# quadcopter.net
KiCad netlist of a schematic drawn in EAGLE
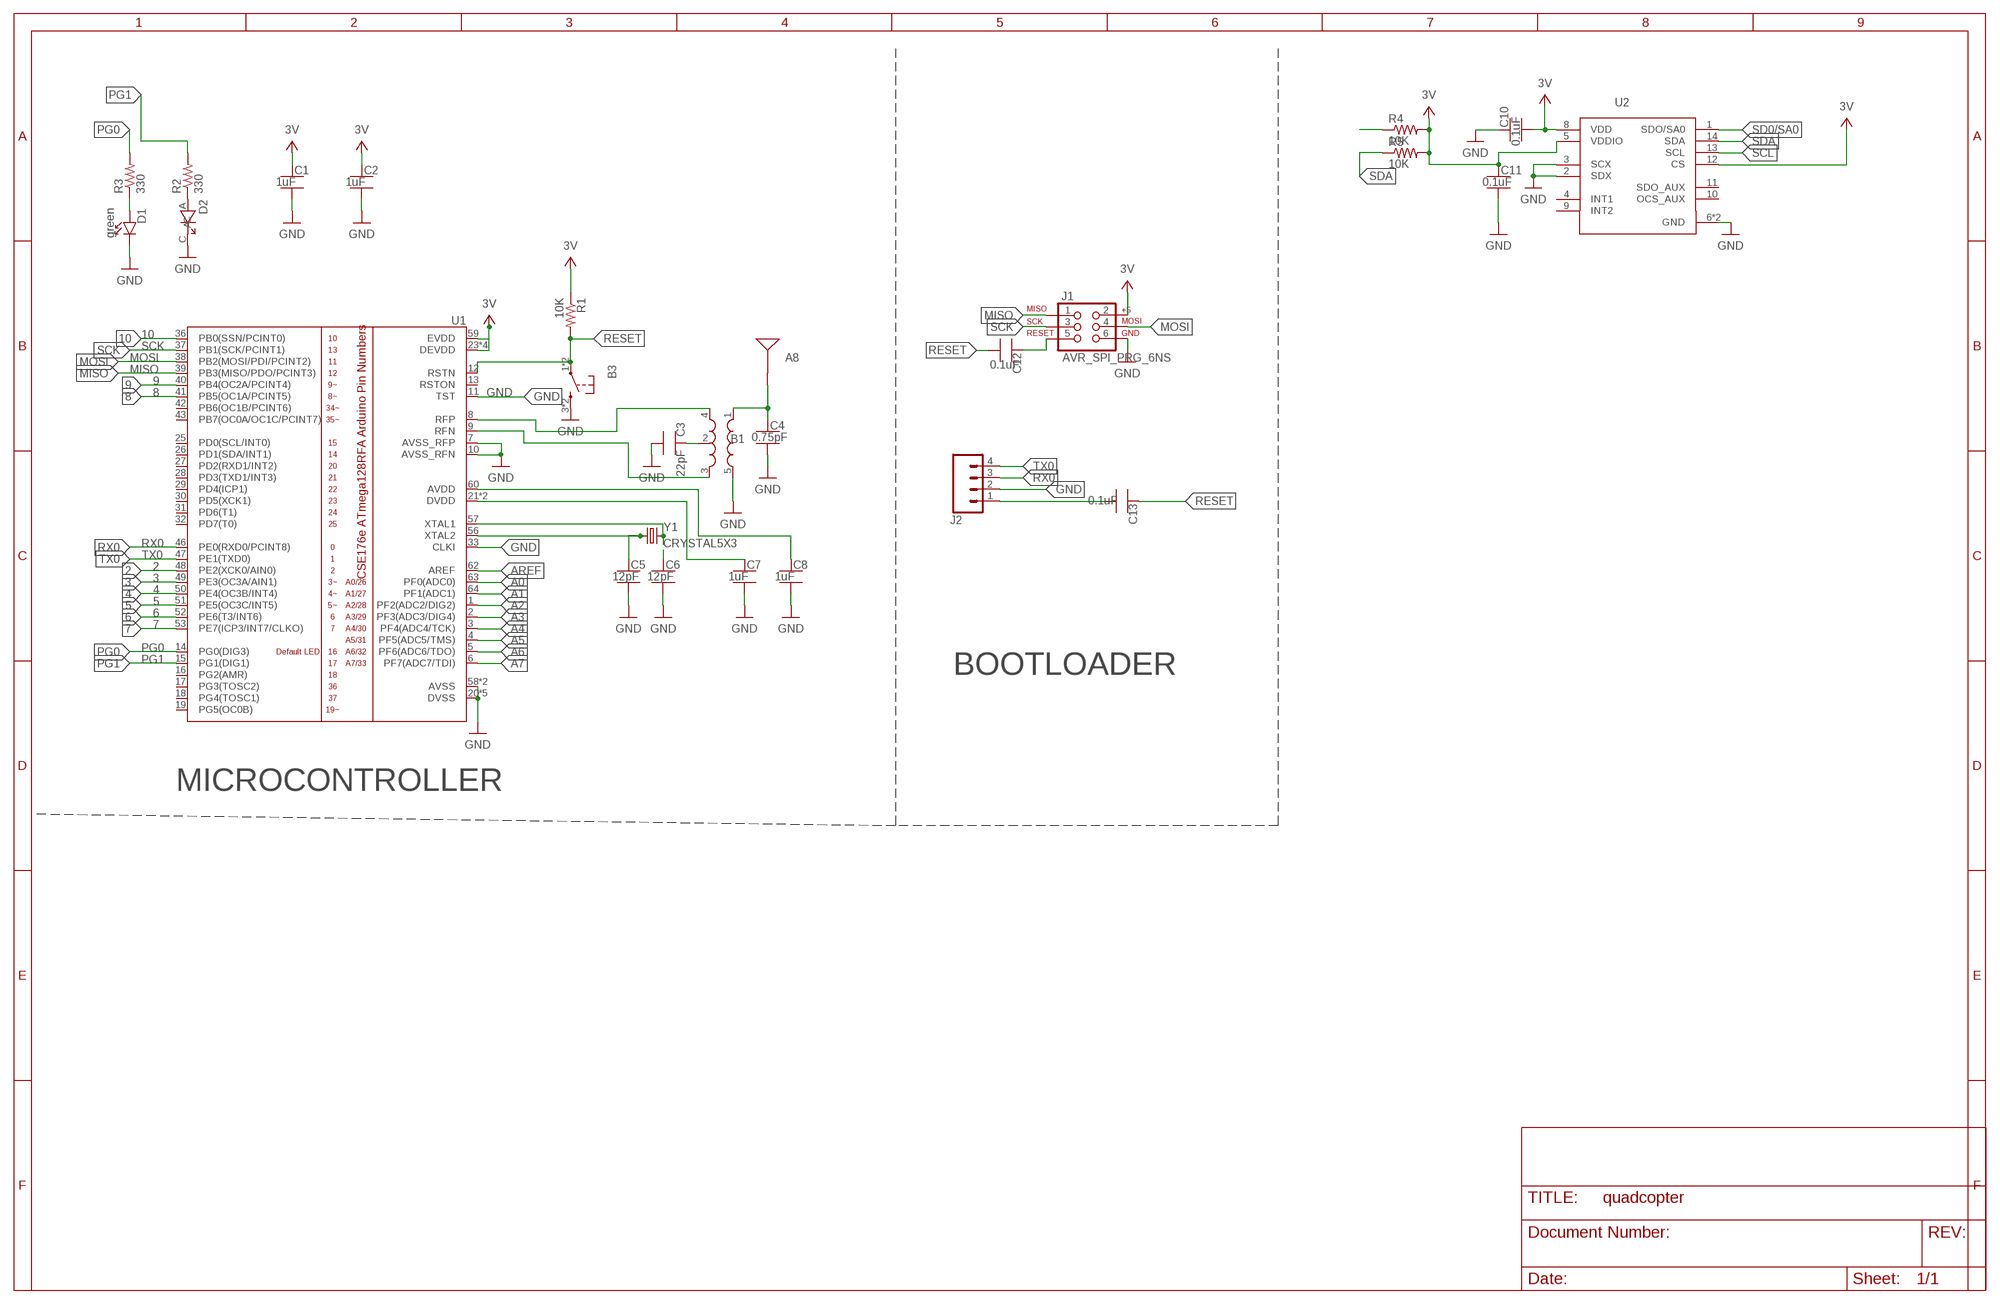
[diagram p0: schematic, sheet 1]

(export (version "E")
  (design (tool "Eeschema 10.0.6"))
  (components
    (comp (ref "A8")
      (value "ANTENNA-BOARD")
      (footprint "eagle-import:ANT_PCB_2.4GHZ_NRF8001_1.6MM_1OZ")
      (fields (field (name "MFR") "NA") (field (name "CREATOR") "Swanson"))
      (libsource (lib "eagle-import") (part "ANTENNA-BOARD"))
    )
    (comp (ref "B1")
      (value "BALUN0805")
      (footprint "eagle-import:BALUN")
      (fields
        (field (name "MFR") "Wurth Electronics Inc.")
        (field (name "MPN") "748421245")
        (field (name "CREATOR") "Swanson")
        (field (name "REVIEWER") "Swanson")
      )
      (libsource (lib "eagle-import") (part "BALUN0805"))
    )
    (comp (ref "B3")
      (value "PUSHBUTTON_SMD-VERTICAL-1")
      (footprint "eagle-import:TE_FSM8JSMA_HS")
      (fields
        (field (name "MFR") "TE Connectivity Alcoswitch Switches")
        (field (name "MPN") "FSM4JSMA")
        (field (name "CREATOR") "Swanson")
        (field (name "REVIEWER") "Swanson")
      )
      (libsource (lib "eagle-import") (part "PUSHBUTTON_SMD-VERTICAL-1"))
    )
    (comp (ref "C1")
      (value "1uF")
      (footprint "eagle-import:CAPC2012X140_HS")
      (fields
        (field (name "MFR") "Taiyo Yuden")
        (field (name "MPN") "TMK212B7105KG-T")
        (field (name "CREATOR") "Swanson")
        (field (name "REVIEWER") "Swanson")
      )
      (libsource (lib "eagle-import") (part "CAPACITOR-NP_SMD-2012-0805_CERAMIC-1UF"))
    )
    (comp (ref "C2")
      (value "1uF")
      (footprint "eagle-import:CAPC2012X140_HS")
      (fields
        (field (name "MFR") "Taiyo Yuden")
        (field (name "MPN") "TMK212B7105KG-T")
        (field (name "CREATOR") "Swanson")
        (field (name "REVIEWER") "Swanson")
      )
      (libsource (lib "eagle-import") (part "CAPACITOR-NP_SMD-2012-0805_CERAMIC-1UF"))
    )
    (comp (ref "C3")
      (value "22pF")
      (footprint "eagle-import:CAPC2012X140_HS")
      (fields
        (field (name "MFR") "Murata Electronics")
        (field (name "MPN") "GRM21A5C2E220JW01D")
        (field (name "CREATOR") "Swanson")
        (field (name "REVIEWER") "Swanson")
      )
      (libsource (lib "eagle-import") (part "CAPACITOR-NP_SMD-2012-0805_CERAMIC-22PF"))
    )
    (comp (ref "C4")
      (value "0.75pF")
      (footprint "eagle-import:CAPC2012X140_HS")
      (fields
        (field (name "MFR") "Murata Electronics")
        (field (name "MPN") "GQM2195C2AR75CB01D")
        (field (name "CREATOR") "Swanson")
        (field (name "REVIEWER") "Swanson")
      )
      (libsource (lib "eagle-import") (part "CAPACITOR-NP_SMD-2012-0805_CERAMIC-0.75PF"))
    )
    (comp (ref "C5")
      (value "12pF")
      (footprint "eagle-import:CAPC2012X140_HS")
      (fields
        (field (name "MFR") "Murata Electronics")
        (field (name "MPN") "GRM21A5C2E120JW01D")
        (field (name "CREATOR") "Swanson")
        (field (name "REVIEWER") "Swanson")
      )
      (libsource (lib "eagle-import") (part "CAPACITOR-NP_SMD-2012-0805_CERAMIC-12PF"))
    )
    (comp (ref "C6")
      (value "12pF")
      (footprint "eagle-import:CAPC2012X140_HS")
      (fields
        (field (name "MFR") "Murata Electronics")
        (field (name "MPN") "GRM21A5C2E120JW01D")
        (field (name "CREATOR") "Swanson")
        (field (name "REVIEWER") "Swanson")
      )
      (libsource (lib "eagle-import") (part "CAPACITOR-NP_SMD-2012-0805_CERAMIC-12PF"))
    )
    (comp (ref "C7")
      (value "1uF")
      (footprint "eagle-import:CAPC2012X140_HS")
      (fields
        (field (name "MFR") "Taiyo Yuden")
        (field (name "MPN") "TMK212B7105KG-T")
        (field (name "CREATOR") "Swanson")
        (field (name "REVIEWER") "Swanson")
      )
      (libsource (lib "eagle-import") (part "CAPACITOR-NP_SMD-2012-0805_CERAMIC-1UF"))
    )
    (comp (ref "C8")
      (value "1uF")
      (footprint "eagle-import:CAPC2012X140_HS")
      (fields
        (field (name "MFR") "Taiyo Yuden")
        (field (name "MPN") "TMK212B7105KG-T")
        (field (name "CREATOR") "Swanson")
        (field (name "REVIEWER") "Swanson")
      )
      (libsource (lib "eagle-import") (part "CAPACITOR-NP_SMD-2012-0805_CERAMIC-1UF"))
    )
    (comp (ref "C10")
      (value "0.1uF")
      (footprint "eagle-import:CAPC2012X140_HS")
      (fields
        (field (name "MFR") "TDK Corporation")
        (field (name "MPN") "C2012X7R2A104K125AA")
        (field (name "CREATOR") "Swanson")
        (field (name "REVIEWER") "Swanson")
      )
      (libsource (lib "eagle-import") (part "CAPACITOR-NP_SMD-2012-0805_CERAMIC-0.1UF"))
    )
    (comp (ref "C11")
      (value "0.1uF")
      (footprint "eagle-import:CAPC2012X140_HS")
      (fields
        (field (name "MFR") "TDK Corporation")
        (field (name "MPN") "C2012X7R2A104K125AA")
        (field (name "CREATOR") "Swanson")
        (field (name "REVIEWER") "Swanson")
      )
      (libsource (lib "eagle-import") (part "CAPACITOR-NP_SMD-2012-0805_CERAMIC-0.1UF"))
    )
    (comp (ref "C12")
      (value "0.1uF")
      (footprint "eagle-import:CAPC2012X140_HS")
      (fields
        (field (name "MFR") "TDK Corporation")
        (field (name "MPN") "C2012X7R2A104K125AA")
        (field (name "CREATOR") "Swanson")
        (field (name "REVIEWER") "Swanson")
      )
      (libsource (lib "eagle-import") (part "CAPACITOR-NP_SMD-2012-0805_CERAMIC-0.1UF"))
    )
    (comp (ref "C13")
      (value "0.1uF")
      (footprint "eagle-import:CAPC2012X140_HS")
      (fields
        (field (name "MFR") "TDK Corporation")
        (field (name "MPN") "C2012X7R2A104K125AA")
        (field (name "CREATOR") "Swanson")
        (field (name "REVIEWER") "Swanson")
      )
      (libsource (lib "eagle-import") (part "CAPACITOR-NP_SMD-2012-0805_CERAMIC-0.1UF"))
    )
    (comp (ref "D1")
      (value "green")
      (footprint "eagle-import:LEDSC125X200X120-2_HS")
      (fields
        (field (name "MFR") "Lite-On Inc")
        (field (name "MPN") "LTST-C170GKT")
        (field (name "CREATOR") "Swanson")
        (field (name "REVIEWER") "Swanson")
      )
      (libsource (lib "eagle-import") (part "DIODE-LED_SMD-2012-0805-GREEN"))
    )
    (comp (ref "D2")
      (value "LED-RED-160-1178-1-ND")
      (footprint "eagle-import:LED_160-1178-1-ND")
      (fields (field (name "CREATOR") "KaustubhKanagalekar"))
      (libsource (lib "eagle-import") (part "LED-RED-160-1178-1-ND"))
    )
    (comp (ref "J1")
      (value "AVR_SPI_PRG_6NS")
      (footprint "eagle-import:2X3-NS")
      (fields
        (field (name "MFR") "Amphenol FCI")
        (field (name "MPN") "67997-206HLF")
        (field (name "CREATOR") "Swanson")
        (field (name "REVIEWER") "Swanson")
      )
      (libsource (lib "eagle-import") (part "AVR_SPI_PRG_6NS"))
    )
    (comp (ref "J2")
      (value "HEADER-4POS-2X2-0.1IN-FEMALE-SMD-BOTTOM-ENTRY")
      (footprint "eagle-import:CONN4_969973-2")
      (fields (field (name "MANUFACTURER_PART_NUMBER") "9699732") (field (name "CREATOR") "DIGIKEY"))
      (libsource (lib "eagle-import") (part "HEADER-4POS-2X2-0.1IN-FEMALE-SMD-BOTTOM-ENTRY"))
    )
    (comp (ref "R1")
      (value "10K")
      (footprint "eagle-import:RESC2012X60_HS")
      (fields
        (field (name "MFR") "Yageo")
        (field (name "MPN") "RC0805JR-0710KL")
        (field (name "CREATOR") "Swanson")
        (field (name "REVIEWER") "Swanson")
      )
      (libsource (lib "eagle-import") (part "RESISTOR_SMD-2012-0805-10K"))
    )
    (comp (ref "R2")
      (value "330")
      (footprint "eagle-import:RESC2012X60_HS")
      (fields
        (field (name "MFR") "Yageo")
        (field (name "MPN") "RC0805JR-07330RL")
        (field (name "CREATOR") "Swanson")
        (field (name "REVIEWER") "Swanson")
      )
      (libsource (lib "eagle-import") (part "RESISTOR_SMD-2012-0805-330"))
    )
    (comp (ref "R3")
      (value "330")
      (footprint "eagle-import:RESC2012X60_HS")
      (fields
        (field (name "MFR") "Yageo")
        (field (name "MPN") "RC0805JR-07330RL")
        (field (name "CREATOR") "Swanson")
        (field (name "REVIEWER") "Swanson")
      )
      (libsource (lib "eagle-import") (part "RESISTOR_SMD-2012-0805-330"))
    )
    (comp (ref "R4")
      (value "10K")
      (footprint "eagle-import:RESC2012X60_HS")
      (fields
        (field (name "MFR") "Yageo")
        (field (name "MPN") "RC0805JR-0710KL")
        (field (name "CREATOR") "Swanson")
        (field (name "REVIEWER") "Swanson")
      )
      (libsource (lib "eagle-import") (part "RESISTOR_SMD-2012-0805-10K"))
    )
    (comp (ref "R5")
      (value "10K")
      (footprint "eagle-import:RESC2012X60_HS")
      (fields
        (field (name "MFR") "Yageo")
        (field (name "MPN") "RC0805JR-0710KL")
        (field (name "CREATOR") "Swanson")
        (field (name "REVIEWER") "Swanson")
      )
      (libsource (lib "eagle-import") (part "RESISTOR_SMD-2012-0805-10K"))
    )
    (comp (ref "U1")
      (value "ATMEGA128RFA1")
      (footprint "eagle-import:QFN-64")
      (fields
        (field (name "MFR") "Microchip Technology")
        (field (name "MPN") "ATMEGA128RFA1-ZU")
        (field (name "CREATOR") "Swanson")
        (field (name "REVIEWER") "Swanson")
      )
      (libsource (lib "eagle-import") (part "ATMEGA128RFA1"))
    )
    (comp (ref "U2")
      (value "IMU-LSM6DSOXTR-497-18367-1-ND497-18367-1-ND")
      (footprint "eagle-import:LSM6DS0")
      (fields (field (name "CREATOR") "KaustubhKanagalekar"))
      (libsource (lib "eagle-import") (part "IMU-LSM6DSOXTR-497-18367-1-ND497-18367-1-ND"))
    )
    (comp (ref "Y1")
      (value "CRYSTAL5X3")
      (footprint "eagle-import:CRYSTAL-SMD-5X3")
      (fields
        (field (name "MFR") "Abracon LLC")
        (field (name "MPN") "ABM3B-16.000MHZ-B2-T")
        (field (name "CREATOR") "Swanson")
        (field (name "REVIEWER") "Swanson")
      )
      (libsource (lib "eagle-import") (part "CRYSTAL5X3"))
    )
  )
  (nets
    (net (code "1") (name "2") (class "Default")
      (node (ref "U1") (pin "48") (pinfunction "PE2(XCK0/AIN0)_48") (pintype "bidirectional"))
    )
    (net (code "2") (name "3") (class "Default")
      (node (ref "U1") (pin "49") (pinfunction "PE3(OC3A/AIN1)_49") (pintype "bidirectional"))
    )
    (net (code "3") (name "3V") (class "Default")
      (node (ref "C1") (pin "1") (pinfunction "1_1") (pintype "passive"))
      (node (ref "C10") (pin "2") (pinfunction "2_2") (pintype "passive"))
      (node (ref "C11") (pin "1") (pinfunction "1_1") (pintype "passive"))
      (node (ref "C2") (pin "1") (pinfunction "1_1") (pintype "passive"))
      (node (ref "J1") (pin "2") (pinfunction "2_2") (pintype "passive"))
      (node (ref "R1") (pin "1") (pinfunction "1_1") (pintype "passive"))
      (node (ref "R4") (pin "2") (pinfunction "2_2") (pintype "passive"))
      (node (ref "R5") (pin "2") (pinfunction "2_2") (pintype "passive"))
      (node (ref "U1") (pin "23") (pinfunction "DEVDD_23") (pintype "bidirectional"))
      (node (ref "U1") (pin "34") (pinfunction "DEVDD_34") (pintype "bidirectional"))
      (node (ref "U1") (pin "44") (pinfunction "DEVDD_44") (pintype "bidirectional"))
      (node (ref "U1") (pin "54") (pinfunction "DEVDD_54") (pintype "bidirectional"))
      (node (ref "U1") (pin "59") (pinfunction "EVDD_59") (pintype "bidirectional"))
      (node (ref "U2") (pin "12") (pinfunction "CS_12") (pintype "bidirectional"))
      (node (ref "U2") (pin "5") (pinfunction "VDDIO_5") (pintype "bidirectional"))
      (node (ref "U2") (pin "8") (pinfunction "VDD_8") (pintype "bidirectional"))
    )
    (net (code "4") (name "4") (class "Default")
      (node (ref "U1") (pin "50") (pinfunction "PE4(OC3B/INT4)_50") (pintype "bidirectional"))
    )
    (net (code "5") (name "5") (class "Default")
      (node (ref "U1") (pin "51") (pinfunction "PE5(OC3C/INT5)_51") (pintype "bidirectional"))
    )
    (net (code "6") (name "6") (class "Default")
      (node (ref "U1") (pin "52") (pinfunction "PE6(T3/INT6)_52") (pintype "bidirectional"))
    )
    (net (code "7") (name "7") (class "Default")
      (node (ref "U1") (pin "53") (pinfunction "PE7(ICP3/INT7/CLKO)_53") (pintype "bidirectional"))
    )
    (net (code "8") (name "8") (class "Default")
      (node (ref "U1") (pin "41") (pinfunction "PB5(OC1A/PCINT5)_41") (pintype "bidirectional"))
    )
    (net (code "9") (name "9") (class "Default")
      (node (ref "U1") (pin "40") (pinfunction "PB4(OC2A/PCINT4)_40") (pintype "bidirectional"))
    )
    (net (code "10") (name "10") (class "Default")
      (node (ref "U1") (pin "36") (pinfunction "PB0(SSN/PCINT0)_36") (pintype "bidirectional"))
    )
    (net (code "11") (name "A0") (class "Default")
      (node (ref "U1") (pin "63") (pinfunction "PF0(ADC0)_63") (pintype "bidirectional"))
    )
    (net (code "12") (name "A1") (class "Default")
      (node (ref "U1") (pin "64") (pinfunction "PF1(ADC1)_64") (pintype "bidirectional"))
    )
    (net (code "13") (name "A2") (class "Default")
      (node (ref "U1") (pin "1") (pinfunction "PF2(ADC2/DIG2)_1") (pintype "bidirectional"))
    )
    (net (code "14") (name "A3") (class "Default")
      (node (ref "U1") (pin "2") (pinfunction "PF3(ADC3/DIG4)_2") (pintype "bidirectional"))
    )
    (net (code "15") (name "A4") (class "Default")
      (node (ref "U1") (pin "3") (pinfunction "PF4(ADC4/TCK)_3") (pintype "bidirectional"))
    )
    (net (code "16") (name "A5") (class "Default")
      (node (ref "U1") (pin "4") (pinfunction "PF5(ADC5/TMS)_4") (pintype "bidirectional"))
    )
    (net (code "17") (name "A6") (class "Default")
      (node (ref "U1") (pin "5") (pinfunction "PF6(ADC6/TDO)_5") (pintype "bidirectional"))
    )
    (net (code "18") (name "A7") (class "Default")
      (node (ref "U1") (pin "6") (pinfunction "PF7(ADC7/TDI)_6") (pintype "bidirectional"))
    )
    (net (code "19") (name "AREF") (class "Default")
      (node (ref "U1") (pin "62") (pinfunction "AREF_62") (pintype "bidirectional"))
    )
    (net (code "20") (name "GND") (class "Default")
      (node (ref "B1") (pin "5") (pinfunction "GND_5") (pintype "bidirectional"))
      (node (ref "B3") (pin "3") (pinfunction "2_3") (pintype "passive"))
      (node (ref "B3") (pin "4") (pinfunction "2_4") (pintype "passive"))
      (node (ref "C1") (pin "2") (pinfunction "2_2") (pintype "passive"))
      (node (ref "C10") (pin "1") (pinfunction "1_1") (pintype "passive"))
      (node (ref "C11") (pin "2") (pinfunction "2_2") (pintype "passive"))
      (node (ref "C2") (pin "2") (pinfunction "2_2") (pintype "passive"))
      (node (ref "C3") (pin "2") (pinfunction "2_2") (pintype "passive"))
      (node (ref "C4") (pin "2") (pinfunction "2_2") (pintype "passive"))
      (node (ref "C5") (pin "2") (pinfunction "2_2") (pintype "passive"))
      (node (ref "C6") (pin "2") (pinfunction "2_2") (pintype "passive"))
      (node (ref "C7") (pin "2") (pinfunction "2_2") (pintype "passive"))
      (node (ref "C8") (pin "2") (pinfunction "2_2") (pintype "passive"))
      (node (ref "D1") (pin "C") (pinfunction "C_C") (pintype "passive"))
      (node (ref "D2") (pin "C") (pinfunction "C_C") (pintype "bidirectional"))
      (node (ref "J1") (pin "6") (pinfunction "6_6") (pintype "passive"))
      (node (ref "J2") (pin "2") (pinfunction "2_2") (pintype "bidirectional"))
      (node (ref "U1") (pin "10") (pinfunction "AVSS_RFN_10") (pintype "bidirectional"))
      (node (ref "U1") (pin "11") (pinfunction "TST_11") (pintype "bidirectional"))
      (node (ref "U1") (pin "20") (pinfunction "DVSS_20") (pintype "bidirectional"))
      (node (ref "U1") (pin "24") (pinfunction "DVSS_24") (pintype "bidirectional"))
      (node (ref "U1") (pin "33") (pinfunction "CLKI_33") (pintype "bidirectional"))
      (node (ref "U1") (pin "35") (pinfunction "DVSS_35") (pintype "bidirectional"))
      (node (ref "U1") (pin "45") (pinfunction "DVSS_45") (pintype "bidirectional"))
      (node (ref "U1") (pin "55") (pinfunction "DVSS_55") (pintype "bidirectional"))
      (node (ref "U1") (pin "58") (pinfunction "AVSS_58") (pintype "bidirectional"))
      (node (ref "U1") (pin "61") (pinfunction "AVSS_61") (pintype "bidirectional"))
      (node (ref "U1") (pin "7") (pinfunction "AVSS_RFP_7") (pintype "bidirectional"))
      (node (ref "U2") (pin "2") (pinfunction "SDX_2") (pintype "bidirectional"))
      (node (ref "U2") (pin "3") (pinfunction "SCX_3") (pintype "bidirectional"))
      (node (ref "U2") (pin "6") (pinfunction "GND_6") (pintype "bidirectional"))
      (node (ref "U2") (pin "7") (pinfunction "GND_7") (pintype "bidirectional"))
    )
    (net (code "21") (name "MISO") (class "Default")
      (node (ref "J1") (pin "1") (pinfunction "1_1") (pintype "passive"))
      (node (ref "U1") (pin "39") (pinfunction "PB3(MISO/PDO/PCINT3)_39") (pintype "bidirectional"))
    )
    (net (code "22") (name "MOSI") (class "Default")
      (node (ref "J1") (pin "4") (pinfunction "4_4") (pintype "passive"))
      (node (ref "U1") (pin "38") (pinfunction "PB2(MOSI/PDI/PCINT2)_38") (pintype "bidirectional"))
    )
    (net (code "23") (name "Net-(A8-SIGNAL)") (class "Default")
      (node (ref "A8") (pin "FEED") (pinfunction "SIGNAL_FEED") (pintype "bidirectional"))
      (node (ref "B1") (pin "1") (pinfunction "IN_1") (pintype "bidirectional"))
      (node (ref "C4") (pin "1") (pinfunction "1_1") (pintype "passive"))
    )
    (net (code "24") (name "Net-(B1-GND-Pad2)") (class "Default")
      (node (ref "B1") (pin "2") (pinfunction "GND_2") (pintype "bidirectional"))
      (node (ref "C3") (pin "1") (pinfunction "1_1") (pintype "passive"))
    )
    (net (code "25") (name "Net-(B1-OUT1)") (class "Default")
      (node (ref "B1") (pin "4") (pinfunction "OUT1_4") (pintype "bidirectional"))
      (node (ref "U1") (pin "8") (pinfunction "RFP_8") (pintype "bidirectional"))
    )
    (net (code "26") (name "Net-(B1-OUT2)") (class "Default")
      (node (ref "B1") (pin "3") (pinfunction "OUT2_3") (pintype "bidirectional"))
      (node (ref "U1") (pin "9") (pinfunction "RFN_9") (pintype "bidirectional"))
    )
    (net (code "27") (name "Net-(C7-Pad1)") (class "Default")
      (node (ref "C7") (pin "1") (pinfunction "1_1") (pintype "passive"))
      (node (ref "U1") (pin "21") (pinfunction "DVDD_21") (pintype "bidirectional"))
      (node (ref "U1") (pin "22") (pinfunction "DVDD_22") (pintype "bidirectional"))
    )
    (net (code "28") (name "Net-(C13-Pad2)") (class "Default")
      (node (ref "C13") (pin "2") (pinfunction "2_2") (pintype "passive"))
      (node (ref "J2") (pin "1") (pinfunction "1_1") (pintype "bidirectional"))
    )
    (net (code "29") (name "Net-(D1-PadA)") (class "Default")
      (node (ref "D1") (pin "A") (pinfunction "A_A") (pintype "passive"))
      (node (ref "R3") (pin "1") (pinfunction "1_1") (pintype "passive"))
    )
    (net (code "30") (name "Net-(D2-PadA)") (class "Default")
      (node (ref "D2") (pin "A") (pinfunction "A_A") (pintype "bidirectional"))
      (node (ref "R2") (pin "1") (pinfunction "1_1") (pintype "passive"))
    )
    (net (code "31") (name "Net-(U1-AVDD)") (class "Default")
      (node (ref "C8") (pin "1") (pinfunction "1_1") (pintype "passive"))
      (node (ref "U1") (pin "60") (pinfunction "AVDD_60") (pintype "bidirectional"))
    )
    (net (code "32") (name "Net-(U1-XTAL1)") (class "Default")
      (node (ref "C6") (pin "1") (pinfunction "1_1") (pintype "passive"))
      (node (ref "U1") (pin "57") (pinfunction "XTAL1_57") (pintype "bidirectional"))
      (node (ref "Y1") (pin "3") (pinfunction "2_3") (pintype "passive"))
    )
    (net (code "33") (name "Net-(U1-XTAL2)") (class "Default")
      (node (ref "C5") (pin "1") (pinfunction "1_1") (pintype "passive"))
      (node (ref "U1") (pin "56") (pinfunction "XTAL2_56") (pintype "bidirectional"))
      (node (ref "Y1") (pin "1") (pinfunction "1_1") (pintype "passive"))
    )
    (net (code "34") (name "PG0") (class "Default")
      (node (ref "R3") (pin "2") (pinfunction "2_2") (pintype "passive"))
      (node (ref "U1") (pin "14") (pinfunction "PG0(DIG3)_14") (pintype "bidirectional"))
    )
    (net (code "35") (name "PG1") (class "Default")
      (node (ref "R2") (pin "2") (pinfunction "2_2") (pintype "passive"))
      (node (ref "U1") (pin "15") (pinfunction "PG1(DIG1)_15") (pintype "bidirectional"))
    )
    (net (code "36") (name "RESET") (class "Default")
      (node (ref "B3") (pin "1") (pinfunction "1_1") (pintype "passive"))
      (node (ref "B3") (pin "2") (pinfunction "1_2") (pintype "passive"))
      (node (ref "C12") (pin "1") (pinfunction "1_1") (pintype "passive"))
      (node (ref "C13") (pin "1") (pinfunction "1_1") (pintype "passive"))
      (node (ref "J1") (pin "5") (pinfunction "5_5") (pintype "passive"))
      (node (ref "R1") (pin "2") (pinfunction "2_2") (pintype "passive"))
      (node (ref "U1") (pin "12") (pinfunction "RSTN_12") (pintype "bidirectional"))
    )
    (net (code "37") (name "RX0") (class "Default")
      (node (ref "J2") (pin "3") (pinfunction "3_3") (pintype "bidirectional"))
      (node (ref "U1") (pin "46") (pinfunction "PE0(RXD0/PCINT8)_46") (pintype "bidirectional"))
    )
    (net (code "38") (name "SCK") (class "Default")
      (node (ref "J1") (pin "3") (pinfunction "3_3") (pintype "passive"))
      (node (ref "U1") (pin "37") (pinfunction "PB1(SCK/PCINT1)_37") (pintype "bidirectional"))
    )
    (net (code "39") (name "SCL") (class "Default")
      (node (ref "U2") (pin "13") (pinfunction "SCL_13") (pintype "bidirectional"))
    )
    (net (code "40") (name "SD0{slash}SA0") (class "Default")
      (node (ref "U2") (pin "1") (pinfunction "SDO/SA0_1") (pintype "bidirectional"))
    )
    (net (code "41") (name "SDA") (class "Default")
      (node (ref "R5") (pin "1") (pinfunction "1_1") (pintype "passive"))
      (node (ref "U2") (pin "14") (pinfunction "SDA_14") (pintype "bidirectional"))
    )
    (net (code "42") (name "TX0") (class "Default")
      (node (ref "J2") (pin "4") (pinfunction "4_4") (pintype "bidirectional"))
      (node (ref "U1") (pin "47") (pinfunction "PE1(TXD0)_47") (pintype "bidirectional"))
    )
    (net (code "43") (name "unconnected-(C12-Pad2)") (class "Default")
      (node (ref "C12") (pin "2") (pinfunction "2_2") (pintype "passive"))
    )
    (net (code "44") (name "unconnected-(R4-Pad1)") (class "Default")
      (node (ref "R4") (pin "1") (pinfunction "1_1") (pintype "passive"))
    )
    (net (code "45") (name "unconnected-(U1-PB6(OC1B{slash}PCINT6)-Pad42)") (class "Default")
      (node (ref "U1") (pin "42") (pinfunction "PB6(OC1B/PCINT6)_42") (pintype "bidirectional"))
    )
    (net (code "46") (name "unconnected-(U1-PB7(OC0A{slash}OC1C{slash}PCINT7)-Pad43)") (class "Default")
      (node (ref "U1") (pin "43") (pinfunction "PB7(OC0A/OC1C/PCINT7)_43") (pintype "bidirectional"))
    )
    (net (code "47") (name "unconnected-(U1-PD0(SCL{slash}INT0)-Pad25)") (class "Default")
      (node (ref "U1") (pin "25") (pinfunction "PD0(SCL/INT0)_25") (pintype "bidirectional"))
    )
    (net (code "48") (name "unconnected-(U1-PD1(SDA{slash}INT1)-Pad26)") (class "Default")
      (node (ref "U1") (pin "26") (pinfunction "PD1(SDA/INT1)_26") (pintype "bidirectional"))
    )
    (net (code "49") (name "unconnected-(U1-PD2(RXD1{slash}INT2)-Pad27)") (class "Default")
      (node (ref "U1") (pin "27") (pinfunction "PD2(RXD1/INT2)_27") (pintype "bidirectional"))
    )
    (net (code "50") (name "unconnected-(U1-PD3(TXD1{slash}INT3)-Pad28)") (class "Default")
      (node (ref "U1") (pin "28") (pinfunction "PD3(TXD1/INT3)_28") (pintype "bidirectional"))
    )
    (net (code "51") (name "unconnected-(U1-PD4(ICP1)-Pad29)") (class "Default")
      (node (ref "U1") (pin "29") (pinfunction "PD4(ICP1)_29") (pintype "bidirectional"))
    )
    (net (code "52") (name "unconnected-(U1-PD5(XCK1)-Pad30)") (class "Default")
      (node (ref "U1") (pin "30") (pinfunction "PD5(XCK1)_30") (pintype "bidirectional"))
    )
    (net (code "53") (name "unconnected-(U1-PD6(T1)-Pad31)") (class "Default")
      (node (ref "U1") (pin "31") (pinfunction "PD6(T1)_31") (pintype "bidirectional"))
    )
    (net (code "54") (name "unconnected-(U1-PD7(T0)-Pad32)") (class "Default")
      (node (ref "U1") (pin "32") (pinfunction "PD7(T0)_32") (pintype "bidirectional"))
    )
    (net (code "55") (name "unconnected-(U1-PG2(AMR)-Pad16)") (class "Default")
      (node (ref "U1") (pin "16") (pinfunction "PG2(AMR)_16") (pintype "bidirectional"))
    )
    (net (code "56") (name "unconnected-(U1-PG3(TOSC2)-Pad17)") (class "Default")
      (node (ref "U1") (pin "17") (pinfunction "PG3(TOSC2)_17") (pintype "bidirectional"))
    )
    (net (code "57") (name "unconnected-(U1-PG4(TOSC1)-Pad18)") (class "Default")
      (node (ref "U1") (pin "18") (pinfunction "PG4(TOSC1)_18") (pintype "bidirectional"))
    )
    (net (code "58") (name "unconnected-(U1-PG5(OC0B)-Pad19)") (class "Default")
      (node (ref "U1") (pin "19") (pinfunction "PG5(OC0B)_19") (pintype "bidirectional"))
    )
    (net (code "59") (name "unconnected-(U1-RSTON-Pad13)") (class "Default")
      (node (ref "U1") (pin "13") (pinfunction "RSTON_13") (pintype "bidirectional"))
    )
    (net (code "60") (name "unconnected-(U2-INT1-Pad4)") (class "Default")
      (node (ref "U2") (pin "4") (pinfunction "INT1_4") (pintype "bidirectional"))
    )
    (net (code "61") (name "unconnected-(U2-INT2-Pad9)") (class "Default")
      (node (ref "U2") (pin "9") (pinfunction "INT2_9") (pintype "bidirectional"))
    )
    (net (code "62") (name "unconnected-(U2-OCS_AUX-Pad10)") (class "Default")
      (node (ref "U2") (pin "10") (pinfunction "OCS_AUX_10") (pintype "bidirectional"))
    )
    (net (code "63") (name "unconnected-(U2-SDO_AUX-Pad11)") (class "Default")
      (node (ref "U2") (pin "11") (pinfunction "SDO_AUX_11") (pintype "bidirectional"))
    )
  )
)
